# 05_FOC_RS_Interface.net
KiCad netlist of a schematic drawn in Altium Designer
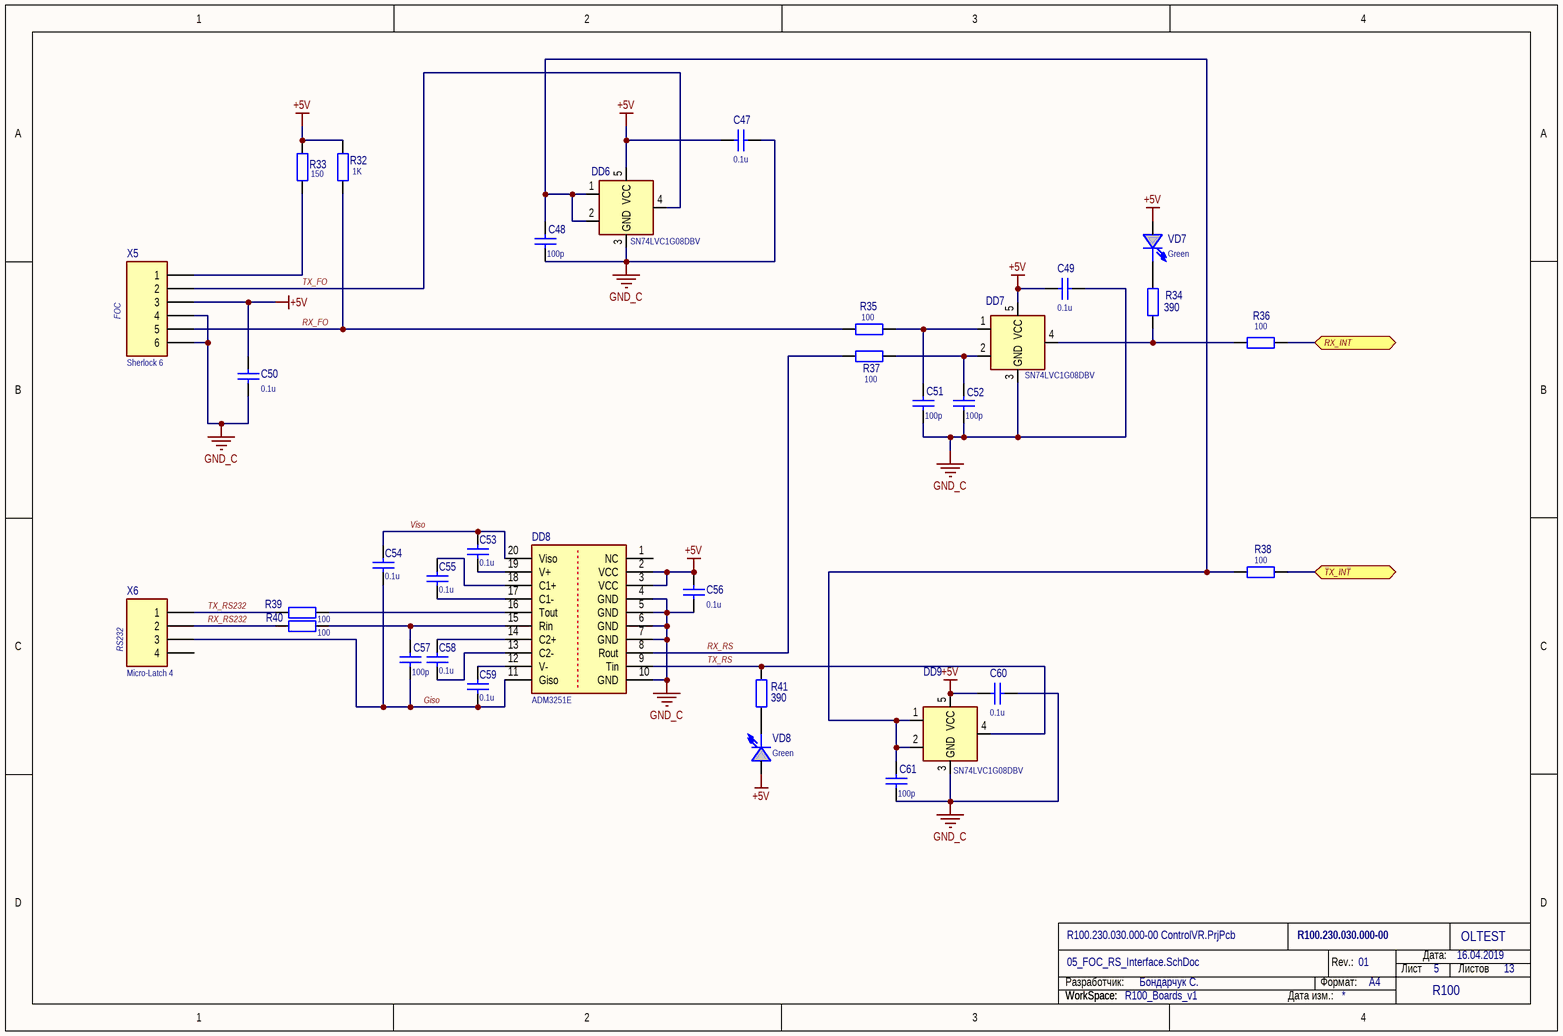
[diagram p0: 05_FOC_RS_Interface.SchDoc]

(export (version "E")
  (design (tool "Eeschema 10.0.6"))
  (components
    (comp (ref "C47")
      (value "0.1u")
      (footprint "mainLib:SMD_C_0603")
      (description "SMD C 0603 MURATA 50V 10% X7R")
      (fields (field (name "PARTNUMBER") "GRM188R71H104K") (field (name "MANUFACTURER") "MURATA"))
      (libsource (lib "mainRCLib") (part "C0603 0.1u 50V 10%"))
    )
    (comp (ref "C48")
      (value "100p")
      (footprint "mainLib:SMD_C_0603")
      (description "SMD C 0603 MURATA 100V 5% NP0")
      (fields (field (name "PARTNUMBER") "GRM1885C2A101JA01") (field (name "MANUFACTURER") "MURATA"))
      (libsource (lib "mainRCLib") (part "C0603 100p 100V 5%"))
    )
    (comp (ref "C49")
      (value "0.1u")
      (footprint "mainLib:SMD_C_0603")
      (description "SMD C 0603 MURATA 50V 10% X7R")
      (fields (field (name "PARTNUMBER") "GRM188R71H104K") (field (name "MANUFACTURER") "MURATA"))
      (libsource (lib "mainRCLib") (part "C0603 0.1u 50V 10%"))
    )
    (comp (ref "C50")
      (value "0.1u")
      (footprint "mainLib:SMD_C_0603")
      (description "SMD C 0603 MURATA 50V 10% X7R")
      (fields (field (name "PARTNUMBER") "GRM188R71H104K") (field (name "MANUFACTURER") "MURATA"))
      (libsource (lib "mainRCLib") (part "C0603 0.1u 50V 10%"))
    )
    (comp (ref "C51")
      (value "100p")
      (footprint "mainLib:SMD_C_0603")
      (description "SMD C 0603 MURATA 100V 5% NP0")
      (fields (field (name "PARTNUMBER") "GRM1885C2A101JA01") (field (name "MANUFACTURER") "MURATA"))
      (libsource (lib "mainRCLib") (part "C0603 100p 100V 5%"))
    )
    (comp (ref "C52")
      (value "100p")
      (footprint "mainLib:SMD_C_0603")
      (description "SMD C 0603 MURATA 100V 5% NP0")
      (fields (field (name "PARTNUMBER") "GRM1885C2A101JA01") (field (name "MANUFACTURER") "MURATA"))
      (libsource (lib "mainRCLib") (part "C0603 100p 100V 5%"))
    )
    (comp (ref "C53")
      (value "0.1u")
      (footprint "mainLib:SMD_C_0603")
      (description "SMD C 0603 MURATA 50V 10% X7R")
      (fields (field (name "PARTNUMBER") "GRM188R71H104K") (field (name "MANUFACTURER") "MURATA"))
      (libsource (lib "mainRCLib") (part "C0603 0.1u 50V 10%"))
    )
    (comp (ref "C54")
      (value "0.1u")
      (footprint "mainLib:SMD_C_0603")
      (description "SMD C 0603 MURATA 50V 10% X7R")
      (fields (field (name "PARTNUMBER") "GRM188R71H104K") (field (name "MANUFACTURER") "MURATA"))
      (libsource (lib "mainRCLib") (part "C0603 0.1u 50V 10%"))
    )
    (comp (ref "C55")
      (value "0.1u")
      (footprint "mainLib:SMD_C_0603")
      (description "SMD C 0603 MURATA 50V 10% X7R")
      (fields (field (name "PARTNUMBER") "GRM188R71H104K") (field (name "MANUFACTURER") "MURATA"))
      (libsource (lib "mainRCLib") (part "C0603 0.1u 50V 10%"))
    )
    (comp (ref "C56")
      (value "0.1u")
      (footprint "mainLib:SMD_C_0603")
      (description "SMD C 0603 MURATA 50V 10% X7R")
      (fields (field (name "PARTNUMBER") "GRM188R71H104K") (field (name "MANUFACTURER") "MURATA"))
      (libsource (lib "mainRCLib") (part "C0603 0.1u 50V 10%"))
    )
    (comp (ref "C57")
      (value "100p")
      (footprint "mainLib:SMD_C_0603")
      (description "SMD C 0603 MURATA 100V 5% NP0")
      (fields (field (name "PARTNUMBER") "GRM1885C2A101JA01") (field (name "MANUFACTURER") "MURATA"))
      (libsource (lib "mainRCLib") (part "C0603 100p 100V 5%"))
    )
    (comp (ref "C58")
      (value "0.1u")
      (footprint "mainLib:SMD_C_0603")
      (description "SMD C 0603 MURATA 50V 10% X7R")
      (fields (field (name "PARTNUMBER") "GRM188R71H104K") (field (name "MANUFACTURER") "MURATA"))
      (libsource (lib "mainRCLib") (part "C0603 0.1u 50V 10%"))
    )
    (comp (ref "C59")
      (value "0.1u")
      (footprint "mainLib:SMD_C_0603")
      (description "SMD C 0603 MURATA 50V 10% X7R")
      (fields (field (name "PARTNUMBER") "GRM188R71H104K") (field (name "MANUFACTURER") "MURATA"))
      (libsource (lib "mainRCLib") (part "C0603 0.1u 50V 10%"))
    )
    (comp (ref "C60")
      (value "0.1u")
      (footprint "mainLib:SMD_C_0603")
      (description "SMD C 0603 MURATA 50V 10% X7R")
      (fields (field (name "PARTNUMBER") "GRM188R71H104K") (field (name "MANUFACTURER") "MURATA"))
      (libsource (lib "mainRCLib") (part "C0603 0.1u 50V 10%"))
    )
    (comp (ref "C61")
      (value "100p")
      (footprint "mainLib:SMD_C_0603")
      (description "SMD C 0603 MURATA 100V 5% NP0")
      (fields (field (name "PARTNUMBER") "GRM1885C2A101JA01") (field (name "MANUFACTURER") "MURATA"))
      (libsource (lib "mainRCLib") (part "C0603 100p 100V 5%"))
    )
    (comp (ref "DD6")
      (value "SN74LVC1G08DBV")
      (footprint "mainLib:SOT-23(DBV)")
      (description "2-in AND")
      (fields (field (name "MANUFACTURER") "Texas Instruments"))
      (libsource (lib "mainLib") (part "SN74LVC1G08DBV"))
    )
    (comp (ref "DD7")
      (value "SN74LVC1G08DBV")
      (footprint "mainLib:SOT-23(DBV)")
      (description "2-in AND")
      (fields (field (name "MANUFACTURER") "Texas Instruments"))
      (libsource (lib "mainLib") (part "SN74LVC1G08DBV"))
    )
    (comp (ref "DD8")
      (value "ADM3251E")
      (footprint "mainLib:RW-20")
      (description "Isolated, Single-Channel, RS-232 Line Driver/Receiver")
      (fields (field (name "MANUFACTURER") "Analog Device") (field (name "PARTNUMBER") "ADM3251EARWZ"))
      (libsource (lib "mainLib") (part "ADM3251E"))
    )
    (comp (ref "DD9")
      (value "SN74LVC1G08DBV")
      (footprint "mainLib:SOT-23(DBV)")
      (description "2-in AND")
      (fields (field (name "MANUFACTURER") "Texas Instruments"))
      (libsource (lib "mainLib") (part "SN74LVC1G08DBV"))
    )
    (comp (ref "R32")
      (value "1K")
      (footprint "mainLib:SMD_R_0603")
      (description "SMD R 0603 VISHAY 0.1W 75V 1% 100ppm")
      (fields (field (name "PARTNUMBER") "CRCW06031K00FK") (field (name "MANUFACTURER") "VISHAY"))
      (libsource (lib "mainRCLib") (part "R0603 1K 1%"))
    )
    (comp (ref "R33")
      (value "150")
      (footprint "mainLib:SMD_R_0805")
      (description "SMD 0805 VISHAY 0.125W 150V 1% 100ppm")
      (fields (field (name "PARTNUMBER") "CRCW0805150RFK") (field (name "MANUFACTURER") "VISHAY"))
      (libsource (lib "mainRCLib") (part "R0805 150 1%"))
    )
    (comp (ref "R34")
      (value "390")
      (footprint "mainLib:SMD_R_0805")
      (description "SMD R 0805 VISHAY 0.125W 150V 1% 100ppm")
      (fields (field (name "PARTNUMBER") "CRCW0805390RFK") (field (name "MANUFACTURER") "VISHAY"))
      (libsource (lib "mainRCLib") (part "R0805 390R 1%"))
    )
    (comp (ref "R35")
      (value "100")
      (footprint "SMD_R_0603")
      (description "SMD R 0603 VISHAY 0.1W 75V 1% 100ppm")
      (fields (field (name "PARTNUMBER") "CRCW0603100RFK") (field (name "MANUFACTURER") "VISHAY"))
      (libsource (lib "mainRCLib") (part "R0603 100 1%"))
    )
    (comp (ref "R36")
      (value "100")
      (footprint "SMD_R_0603")
      (description "SMD R 0603 VISHAY 0.1W 75V 1% 100ppm")
      (fields (field (name "PARTNUMBER") "CRCW0603100RFK") (field (name "MANUFACTURER") "VISHAY"))
      (libsource (lib "mainRCLib") (part "R0603 100 1%"))
    )
    (comp (ref "R37")
      (value "100")
      (footprint "SMD_R_0603")
      (description "SMD R 0603 VISHAY 0.1W 75V 1% 100ppm")
      (fields (field (name "PARTNUMBER") "CRCW0603100RFK") (field (name "MANUFACTURER") "VISHAY"))
      (libsource (lib "mainRCLib") (part "R0603 100 1%"))
    )
    (comp (ref "R38")
      (value "100")
      (footprint "SMD_R_0603")
      (description "SMD R 0603 VISHAY 0.1W 75V 1% 100ppm")
      (fields (field (name "PARTNUMBER") "CRCW0603100RFK") (field (name "MANUFACTURER") "VISHAY"))
      (libsource (lib "mainRCLib") (part "R0603 100 1%"))
    )
    (comp (ref "R39")
      (value "100")
      (footprint "SMD_R_0603")
      (description "SMD R 0603 VISHAY 0.1W 75V 1% 100ppm")
      (fields (field (name "PARTNUMBER") "CRCW0603100RFK") (field (name "MANUFACTURER") "VISHAY"))
      (libsource (lib "mainRCLib") (part "R0603 100 1%"))
    )
    (comp (ref "R40")
      (value "100")
      (footprint "SMD_R_0603")
      (description "SMD R 0603 VISHAY 0.1W 75V 1% 100ppm")
      (fields (field (name "PARTNUMBER") "CRCW0603100RFK") (field (name "MANUFACTURER") "VISHAY"))
      (libsource (lib "mainRCLib") (part "R0603 100 1%"))
    )
    (comp (ref "R41")
      (value "390")
      (footprint "mainLib:SMD_R_0805")
      (description "SMD R 0805 VISHAY 0.125W 150V 1% 100ppm")
      (fields (field (name "PARTNUMBER") "CRCW0805390RFK") (field (name "MANUFACTURER") "VISHAY"))
      (libsource (lib "mainRCLib") (part "R0805 390R 1%"))
    )
    (comp (ref "VD7")
      (value "Green")
      (footprint "mainLib:SMD_LED_LL_Green")
      (description "LED Green SMD")
      (fields (field (name "PARTNUMBER") "LL-S172GC-2A") (field (name "MANUFACTURER") "Lucky Light"))
      (libsource (lib "mainLib") (part "LL-S172GC-2A"))
    )
    (comp (ref "VD8")
      (value "Green")
      (footprint "mainLib:SMD_LED_LL_Green")
      (description "LED Green SMD")
      (fields (field (name "PARTNUMBER") "LL-S172GC-2A") (field (name "MANUFACTURER") "Lucky Light"))
      (libsource (lib "mainLib") (part "LL-S172GC-2A"))
    )
    (comp (ref "X5")
      (value "Sherlock 6")
      (footprint "mainLib:35362-0650")
      (description "Sherlock 6 Side, 2A 125V 2mm")
      (fields (field (name "PARTNUMBER") "35362-0650") (field (name "MANUFACTURER") "MOLEX"))
      (libsource (lib "mainLib") (part "35363-0650"))
    )
    (comp (ref "X6")
      (value "Micro-Latch 4")
      (footprint "mainLib:53253-0470")
      (description "Micro-Latch 4  LS=2 2A 125V PCB")
      (fields (field (name "PARTNUMBER") "53253-0470") (field (name "MANUFACTURER") "MOLEX"))
      (libsource (lib "mainLib") (part "53253-0470"))
    )
  )
  (nets
    (net (code "1") (name "+5V") (class "Default")
      (node (ref "C47") (pin "1") (pinfunction "1_1") (pintype "passive"))
      (node (ref "C49") (pin "1") (pinfunction "1_1") (pintype "passive"))
      (node (ref "C50") (pin "2") (pinfunction "2_2") (pintype "passive"))
      (node (ref "C56") (pin "2") (pinfunction "2_2") (pintype "passive"))
      (node (ref "C60") (pin "1") (pinfunction "1_1") (pintype "passive"))
      (node (ref "DD6") (pin "5") (pinfunction "VCC_5") (pintype "passive"))
      (node (ref "DD7") (pin "5") (pinfunction "VCC_5") (pintype "passive"))
      (node (ref "DD8") (pin "2") (pinfunction "VCC_2") (pintype "power_in"))
      (node (ref "DD8") (pin "3") (pinfunction "VCC_3") (pintype "power_in"))
      (node (ref "DD9") (pin "5") (pinfunction "VCC_5") (pintype "passive"))
      (node (ref "R32") (pin "2") (pinfunction "2_2") (pintype "passive"))
      (node (ref "R33") (pin "2") (pinfunction "2_2") (pintype "passive"))
      (node (ref "VD7") (pin "1") (pinfunction "ANODE_1") (pintype "passive"))
      (node (ref "VD8") (pin "1") (pinfunction "ANODE_1") (pintype "passive"))
      (node (ref "X5") (pin "3") (pinfunction "3_3") (pintype "passive"))
    )
    (net (code "2") (name "/Giso") (class "Default")
      (node (ref "C54") (pin "1") (pinfunction "1_1") (pintype "passive"))
      (node (ref "C57") (pin "1") (pinfunction "1_1") (pintype "passive"))
      (node (ref "C59") (pin "1") (pinfunction "1_1") (pintype "passive"))
      (node (ref "DD8") (pin "11") (pinfunction "Giso_11") (pintype "passive"))
      (node (ref "X6") (pin "3") (pinfunction "3_3") (pintype "passive"))
    )
    (net (code "3") (name "/RX_FO") (class "Default")
      (node (ref "R32") (pin "1") (pinfunction "1_1") (pintype "passive"))
      (node (ref "R35") (pin "1") (pinfunction "1_1") (pintype "passive"))
      (node (ref "X5") (pin "5") (pinfunction "5_5") (pintype "passive"))
    )
    (net (code "4") (name "/RX_INT") (class "Default")
      (node (ref "R36") (pin "2") (pinfunction "2_2") (pintype "passive"))
    )
    (net (code "5") (name "/RX_RS") (class "Default")
      (node (ref "DD8") (pin "8") (pinfunction "Rout_8") (pintype "passive"))
      (node (ref "R37") (pin "1") (pinfunction "1_1") (pintype "passive"))
    )
    (net (code "6") (name "/RX_RS232") (class "Default")
      (node (ref "R40") (pin "1") (pinfunction "1_1") (pintype "passive"))
      (node (ref "X6") (pin "2") (pinfunction "2_2") (pintype "passive"))
    )
    (net (code "7") (name "/TX_FO") (class "Default")
      (node (ref "DD6") (pin "4") (pintype "passive"))
      (node (ref "X5") (pin "2") (pinfunction "2_2") (pintype "passive"))
    )
    (net (code "8") (name "/TX_INT") (class "Default")
      (node (ref "R38") (pin "2") (pinfunction "2_2") (pintype "passive"))
    )
    (net (code "9") (name "/TX_RS") (class "Default")
      (node (ref "DD8") (pin "9") (pinfunction "Tin_9") (pintype "passive"))
      (node (ref "DD9") (pin "4") (pintype "passive"))
      (node (ref "R41") (pin "2") (pinfunction "2_2") (pintype "passive"))
    )
    (net (code "10") (name "/TX_RS232") (class "Default")
      (node (ref "R39") (pin "1") (pinfunction "1_1") (pintype "passive"))
      (node (ref "X6") (pin "1") (pinfunction "1_1") (pintype "passive"))
    )
    (net (code "11") (name "/Viso") (class "Default")
      (node (ref "C53") (pin "2") (pinfunction "2_2") (pintype "passive"))
      (node (ref "C54") (pin "2") (pinfunction "2_2") (pintype "passive"))
      (node (ref "DD8") (pin "20") (pinfunction "Viso_20") (pintype "passive"))
    )
    (net (code "12") (name "GND_C") (class "Default")
      (node (ref "C47") (pin "2") (pinfunction "2_2") (pintype "passive"))
      (node (ref "C48") (pin "1") (pinfunction "1_1") (pintype "passive"))
      (node (ref "C49") (pin "2") (pinfunction "2_2") (pintype "passive"))
      (node (ref "C50") (pin "1") (pinfunction "1_1") (pintype "passive"))
      (node (ref "C51") (pin "1") (pinfunction "1_1") (pintype "passive"))
      (node (ref "C52") (pin "2") (pinfunction "2_2") (pintype "passive"))
      (node (ref "C56") (pin "1") (pinfunction "1_1") (pintype "passive"))
      (node (ref "C60") (pin "2") (pinfunction "2_2") (pintype "passive"))
      (node (ref "C61") (pin "1") (pinfunction "1_1") (pintype "passive"))
      (node (ref "DD6") (pin "3") (pinfunction "GND_3") (pintype "passive"))
      (node (ref "DD7") (pin "3") (pinfunction "GND_3") (pintype "passive"))
      (node (ref "DD8") (pin "10") (pinfunction "GND_10") (pintype "power_in"))
      (node (ref "DD8") (pin "4") (pinfunction "GND_4") (pintype "power_in"))
      (node (ref "DD8") (pin "5") (pinfunction "GND_5") (pintype "power_in"))
      (node (ref "DD8") (pin "6") (pinfunction "GND_6") (pintype "power_in"))
      (node (ref "DD8") (pin "7") (pinfunction "GND_7") (pintype "power_in"))
      (node (ref "DD9") (pin "3") (pinfunction "GND_3") (pintype "passive"))
      (node (ref "X5") (pin "4") (pinfunction "4_4") (pintype "passive"))
      (node (ref "X5") (pin "6") (pinfunction "6_6") (pintype "passive"))
    )
    (net (code "13") (name "Net-(C48-Pad2)") (class "Default")
      (node (ref "C48") (pin "2") (pinfunction "2_2") (pintype "passive"))
      (node (ref "C61") (pin "2") (pinfunction "2_2") (pintype "passive"))
      (node (ref "DD6") (pin "1") (pintype "passive"))
      (node (ref "DD6") (pin "2") (pintype "passive"))
      (node (ref "DD9") (pin "1") (pintype "passive"))
      (node (ref "DD9") (pin "2") (pintype "passive"))
      (node (ref "R38") (pin "1") (pinfunction "1_1") (pintype "passive"))
    )
    (net (code "14") (name "Net-(C51-Pad2)") (class "Default")
      (node (ref "C51") (pin "2") (pinfunction "2_2") (pintype "passive"))
      (node (ref "DD7") (pin "1") (pintype "passive"))
      (node (ref "R35") (pin "2") (pinfunction "2_2") (pintype "passive"))
    )
    (net (code "15") (name "Net-(C52-Pad1)") (class "Default")
      (node (ref "C52") (pin "1") (pinfunction "1_1") (pintype "passive"))
      (node (ref "DD7") (pin "2") (pintype "passive"))
      (node (ref "R37") (pin "2") (pinfunction "2_2") (pintype "passive"))
    )
    (net (code "16") (name "Net-(DD7-Pad4)") (class "Default")
      (node (ref "DD7") (pin "4") (pintype "passive"))
      (node (ref "R34") (pin "1") (pinfunction "1_1") (pintype "passive"))
      (node (ref "R36") (pin "1") (pinfunction "1_1") (pintype "passive"))
    )
    (net (code "17") (name "Net-(DD8-C1+)") (class "Default")
      (node (ref "C55") (pin "2") (pinfunction "2_2") (pintype "passive"))
      (node (ref "DD8") (pin "18") (pinfunction "C1+_18") (pintype "passive"))
    )
    (net (code "18") (name "Net-(DD8-C1-)") (class "Default")
      (node (ref "C55") (pin "1") (pinfunction "1_1") (pintype "passive"))
      (node (ref "DD8") (pin "17") (pinfunction "C1-_17") (pintype "passive"))
    )
    (net (code "19") (name "Net-(DD8-C2+)") (class "Default")
      (node (ref "C58") (pin "2") (pinfunction "2_2") (pintype "passive"))
      (node (ref "DD8") (pin "14") (pinfunction "C2+_14") (pintype "passive"))
    )
    (net (code "20") (name "Net-(DD8-C2-)") (class "Default")
      (node (ref "C58") (pin "1") (pinfunction "1_1") (pintype "passive"))
      (node (ref "DD8") (pin "13") (pinfunction "C2-_13") (pintype "passive"))
    )
    (net (code "21") (name "Net-(DD8-Rin)") (class "Default")
      (node (ref "C57") (pin "2") (pinfunction "2_2") (pintype "passive"))
      (node (ref "DD8") (pin "15") (pinfunction "Rin_15") (pintype "passive"))
      (node (ref "R40") (pin "2") (pinfunction "2_2") (pintype "passive"))
    )
    (net (code "22") (name "Net-(DD8-Tout)") (class "Default")
      (node (ref "DD8") (pin "16") (pinfunction "Tout_16") (pintype "passive"))
      (node (ref "R39") (pin "2") (pinfunction "2_2") (pintype "passive"))
    )
    (net (code "23") (name "Net-(DD8-V+)") (class "Default")
      (node (ref "C53") (pin "1") (pinfunction "1_1") (pintype "passive"))
      (node (ref "DD8") (pin "19") (pinfunction "V+_19") (pintype "passive"))
    )
    (net (code "24") (name "Net-(DD8-V-)") (class "Default")
      (node (ref "C59") (pin "2") (pinfunction "2_2") (pintype "passive"))
      (node (ref "DD8") (pin "12") (pinfunction "V-_12") (pintype "passive"))
    )
    (net (code "25") (name "Net-(R33-Pad1)") (class "Default")
      (node (ref "R33") (pin "1") (pinfunction "1_1") (pintype "passive"))
      (node (ref "X5") (pin "1") (pinfunction "1_1") (pintype "passive"))
    )
    (net (code "26") (name "Net-(VD7-CATHODE)") (class "Default")
      (node (ref "R34") (pin "2") (pinfunction "2_2") (pintype "passive"))
      (node (ref "VD7") (pin "2") (pinfunction "CATHODE_2") (pintype "passive"))
    )
    (net (code "27") (name "Net-(VD8-CATHODE)") (class "Default")
      (node (ref "R41") (pin "1") (pinfunction "1_1") (pintype "passive"))
      (node (ref "VD8") (pin "2") (pinfunction "CATHODE_2") (pintype "passive"))
    )
    (net (code "28") (name "unconnected-(DD8-NC-Pad1)") (class "Default")
      (node (ref "DD8") (pin "1") (pinfunction "NC_1") (pintype "passive"))
    )
    (net (code "29") (name "unconnected-(X6-Pad4)") (class "Default")
      (node (ref "X6") (pin "4") (pinfunction "4_4") (pintype "passive"))
    )
  )
)
